# CircuitPlayground_ESP12_555_004.net
KiCad netlist of a schematic drawn in EAGLE
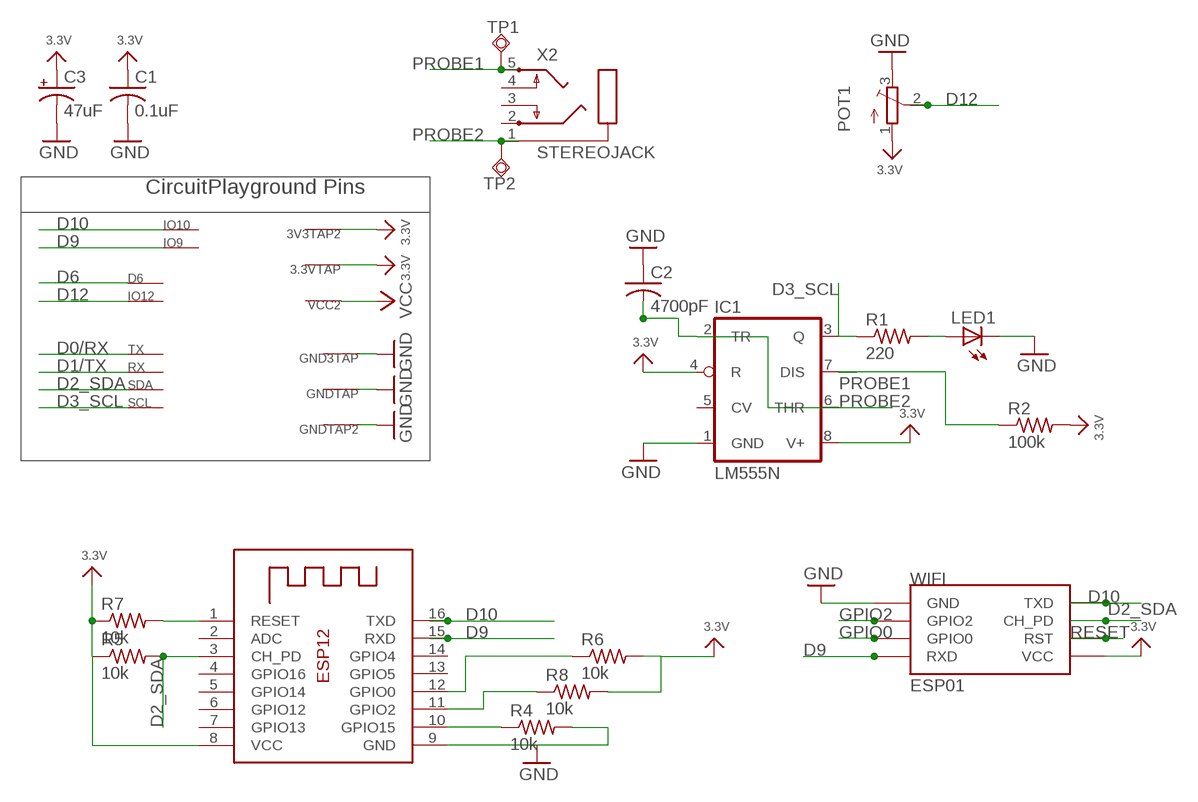
[diagram p0: schematic, sheet 1]

(export (version "E")
  (design (tool "Eeschema 10.0.6"))
  (components
    (comp (ref "3.3VTAP")
      (value "SEWTAP-ALLIGATOR")
      (footprint "eagle-import:SEWALLI")
      (libsource (lib "eagle-import") (part "SEWTAP-ALLIGATOR"))
    )
    (comp (ref "3V3TAP2")
      (value "SEWTAP-ALLIGATOR")
      (footprint "eagle-import:SEWALLI")
      (libsource (lib "eagle-import") (part "SEWTAP-ALLIGATOR"))
    )
    (comp (ref "C1")
      (value "0.1uF")
      (footprint "eagle-import:C025-030X050")
      (libsource (lib "eagle-import") (part "C-US025-030X050"))
    )
    (comp (ref "C2")
      (value "4700pF")
      (footprint "eagle-import:C025-030X050")
      (libsource (lib "eagle-import") (part "C-US025-030X050"))
    )
    (comp (ref "C3")
      (value "47uF")
      (footprint "eagle-import:E2-4")
      (libsource (lib "eagle-import") (part "CPOL-USE2-4"))
    )
    (comp (ref "D6")
      (value "SEWTAP-ALLIGATOR")
      (footprint "eagle-import:SEWALLI")
      (libsource (lib "eagle-import") (part "SEWTAP-ALLIGATOR"))
    )
    (comp (ref "GND3TAP")
      (value "SEWTAP-ALLIGATOR")
      (footprint "eagle-import:SEWALLI")
      (libsource (lib "eagle-import") (part "SEWTAP-ALLIGATOR"))
    )
    (comp (ref "GNDTAP")
      (value "SEWTAP-ALLIGATOR")
      (footprint "eagle-import:SEWALLI")
      (libsource (lib "eagle-import") (part "SEWTAP-ALLIGATOR"))
    )
    (comp (ref "GNDTAP2")
      (value "SEWTAP-ALLIGATOR")
      (footprint "eagle-import:SEWALLI")
      (libsource (lib "eagle-import") (part "SEWTAP-ALLIGATOR"))
    )
    (comp (ref "IC1")
      (value "LM555N")
      (footprint "eagle-import:DIL08-ROUND")
      (libsource (lib "eagle-import") (part "555NLM"))
    )
    (comp (ref "IO9")
      (value "SEWTAP-ALLIGATOR")
      (footprint "eagle-import:SEWALLI")
      (libsource (lib "eagle-import") (part "SEWTAP-ALLIGATOR"))
    )
    (comp (ref "IO10")
      (value "SEWTAP-ALLIGATOR")
      (footprint "eagle-import:SEWALLI")
      (libsource (lib "eagle-import") (part "SEWTAP-ALLIGATOR"))
    )
    (comp (ref "IO12")
      (value "SEWTAP-ALLIGATOR")
      (footprint "eagle-import:SEWALLI")
      (libsource (lib "eagle-import") (part "SEWTAP-ALLIGATOR"))
    )
    (comp (ref "LED1")
      (value "LED5MM")
      (footprint "eagle-import:LED5MM")
      (libsource (lib "eagle-import") (part "LED5MM"))
    )
    (comp (ref "POT1")
      (value "TRIMPOT3386")
      (footprint "eagle-import:TRIM-3386")
      (libsource (lib "eagle-import") (part "TRIMPOT3386"))
    )
    (comp (ref "R1")
      (value "220")
      (footprint "eagle-import:R1206")
      (libsource (lib "eagle-import") (part "R-US_R1206"))
    )
    (comp (ref "R2")
      (value "100k")
      (footprint "eagle-import:R1206")
      (libsource (lib "eagle-import") (part "R-US_R1206"))
    )
    (comp (ref "R4")
      (value "10k")
      (footprint "eagle-import:R1206")
      (libsource (lib "eagle-import") (part "R-US_R1206"))
    )
    (comp (ref "R5")
      (value "10k")
      (footprint "eagle-import:R1206")
      (libsource (lib "eagle-import") (part "R-US_R1206"))
    )
    (comp (ref "R6")
      (value "10k")
      (footprint "eagle-import:R1206")
      (libsource (lib "eagle-import") (part "R-US_R1206"))
    )
    (comp (ref "R7")
      (value "10k")
      (footprint "eagle-import:R1206")
      (libsource (lib "eagle-import") (part "R-US_R1206"))
    )
    (comp (ref "R8")
      (value "10k")
      (footprint "eagle-import:R1206")
      (libsource (lib "eagle-import") (part "R-US_R1206"))
    )
    (comp (ref "RX")
      (value "SEWTAP-ALLIGATOR")
      (footprint "eagle-import:SEWALLI")
      (libsource (lib "eagle-import") (part "SEWTAP-ALLIGATOR"))
    )
    (comp (ref "SCL")
      (value "SEWTAP-ALLIGATOR")
      (footprint "eagle-import:SEWALLI")
      (libsource (lib "eagle-import") (part "SEWTAP-ALLIGATOR"))
    )
    (comp (ref "SDA")
      (value "SEWTAP-ALLIGATOR")
      (footprint "eagle-import:SEWALLI")
      (libsource (lib "eagle-import") (part "SEWTAP-ALLIGATOR"))
    )
    (comp (ref "TP1")
      (value "TPSQTP20R")
      (footprint "eagle-import:TP20R")
      (libsource (lib "eagle-import") (part "TPSQTP20R"))
    )
    (comp (ref "TP2")
      (value "TPSQTP20R")
      (footprint "eagle-import:TP20R")
      (libsource (lib "eagle-import") (part "TPSQTP20R"))
    )
    (comp (ref "TX")
      (value "SEWTAP-ALLIGATOR")
      (footprint "eagle-import:SEWALLI")
      (libsource (lib "eagle-import") (part "SEWTAP-ALLIGATOR"))
    )
    (comp (ref "VCC2")
      (value "SEWTAP-ALLIGATOR")
      (footprint "eagle-import:SEWALLI")
      (libsource (lib "eagle-import") (part "SEWTAP-ALLIGATOR"))
    )
    (comp (ref "WIFI")
      (value "ESP01")
      (footprint "eagle-import:ESP01")
      (libsource (lib "eagle-import") (part "ESP01"))
    )
    (comp (ref "X1")
      (value "ESP-12")
      (footprint "eagle-import:ESP-12")
      (libsource (lib "eagle-import") (part "ESP-12"))
    )
    (comp (ref "X2")
      (value "STEREOJACK")
      (footprint "eagle-import:STX3100")
      (libsource (lib "eagle-import") (part "STEREOJACK"))
    )
  )
  (nets
    (net (code "1") (name "/D0{slash}RX") (class "Default")
      (node (ref "TX") (pin "P$1") (pinfunction "SEW_P$1") (pintype "bidirectional"))
    )
    (net (code "2") (name "/D1{slash}TX") (class "Default")
      (node (ref "RX") (pin "P$1") (pinfunction "SEW_P$1") (pintype "bidirectional"))
    )
    (net (code "3") (name "/D2_SDA") (class "Default")
      (node (ref "R5") (pin "2") (pinfunction "2_2") (pintype "passive"))
      (node (ref "SDA") (pin "P$1") (pinfunction "SEW_P$1") (pintype "bidirectional"))
      (node (ref "WIFI") (pin "CH_PD") (pinfunction "CH_PD_CH_PD") (pintype "bidirectional"))
      (node (ref "X1") (pin "3") (pinfunction "CH_PD_3") (pintype "input"))
    )
    (net (code "4") (name "/D3_SCL") (class "Default")
      (node (ref "IC1") (pin "3") (pinfunction "Q_3") (pintype "output"))
      (node (ref "R1") (pin "1") (pinfunction "1_1") (pintype "passive"))
      (node (ref "SCL") (pin "P$1") (pinfunction "SEW_P$1") (pintype "bidirectional"))
    )
    (net (code "5") (name "/D6") (class "Default")
      (node (ref "D6") (pin "P$1") (pinfunction "SEW_P$1") (pintype "bidirectional"))
    )
    (net (code "6") (name "/D9") (class "Default")
      (node (ref "IO9") (pin "P$1") (pinfunction "SEW_P$1") (pintype "bidirectional"))
      (node (ref "WIFI") (pin "RX") (pinfunction "RXD_RX") (pintype "bidirectional"))
      (node (ref "X1") (pin "15") (pinfunction "RXD_15") (pintype "input"))
    )
    (net (code "7") (name "/D10") (class "Default")
      (node (ref "IO10") (pin "P$1") (pinfunction "SEW_P$1") (pintype "bidirectional"))
      (node (ref "WIFI") (pin "TX") (pinfunction "TXD_TX") (pintype "bidirectional"))
      (node (ref "X1") (pin "16") (pinfunction "TXD_16") (pintype "output"))
    )
    (net (code "8") (name "/D12") (class "Default")
      (node (ref "IO12") (pin "P$1") (pinfunction "SEW_P$1") (pintype "bidirectional"))
      (node (ref "POT1") (pin "2") (pinfunction "S_2") (pintype "passive"))
    )
    (net (code "9") (name "/GPIO0") (class "Default")
      (node (ref "R6") (pin "1") (pinfunction "1_1") (pintype "passive"))
      (node (ref "WIFI") (pin "GPIO0") (pinfunction "GPIO0_GPIO0") (pintype "bidirectional"))
      (node (ref "X1") (pin "12") (pinfunction "GPIO0_12") (pintype "bidirectional"))
    )
    (net (code "10") (name "/GPIO2") (class "Default")
      (node (ref "R8") (pin "1") (pinfunction "1_1") (pintype "passive"))
      (node (ref "WIFI") (pin "GPIO2") (pinfunction "GPIO2_GPIO2") (pintype "bidirectional"))
      (node (ref "X1") (pin "11") (pinfunction "GPIO2_11") (pintype "bidirectional"))
    )
    (net (code "11") (name "/PROBE1") (class "Default")
      (node (ref "IC1") (pin "7") (pinfunction "DIS_7") (pintype "input"))
      (node (ref "R2") (pin "1") (pinfunction "1_1") (pintype "passive"))
      (node (ref "TP1") (pin "TP") (pinfunction "TP_TP") (pintype "input"))
      (node (ref "X2") (pin "5") (pinfunction "5_5") (pintype "passive"))
    )
    (net (code "12") (name "/PROBE2") (class "Default")
      (node (ref "C2") (pin "2") (pinfunction "2_2") (pintype "passive"))
      (node (ref "IC1") (pin "2") (pinfunction "TR_2") (pintype "input"))
      (node (ref "IC1") (pin "6") (pinfunction "THR_6") (pintype "input"))
      (node (ref "TP2") (pin "TP") (pinfunction "TP_TP") (pintype "input"))
      (node (ref "X2") (pin "1") (pinfunction "1_1") (pintype "passive"))
    )
    (net (code "13") (name "/RESET") (class "Default")
      (node (ref "R7") (pin "2") (pinfunction "2_2") (pintype "passive"))
      (node (ref "WIFI") (pin "RST") (pinfunction "RST_RST") (pintype "bidirectional"))
      (node (ref "X1") (pin "1") (pinfunction "RESET_1") (pintype "input"))
    )
    (net (code "14") (name "3.3V") (class "Default")
      (node (ref "3.3VTAP") (pin "P$1") (pinfunction "SEW_P$1") (pintype "bidirectional"))
      (node (ref "3V3TAP2") (pin "P$1") (pinfunction "SEW_P$1") (pintype "bidirectional"))
      (node (ref "C1") (pin "1") (pinfunction "1_1") (pintype "passive"))
      (node (ref "C3") (pin "+") (pinfunction "+_+") (pintype "passive"))
      (node (ref "IC1") (pin "4") (pinfunction "R_4") (pintype "input"))
      (node (ref "IC1") (pin "8") (pinfunction "V+_8") (pintype "power_in"))
      (node (ref "POT1") (pin "1") (pinfunction "A_1") (pintype "passive"))
      (node (ref "R2") (pin "2") (pinfunction "2_2") (pintype "passive"))
      (node (ref "R5") (pin "1") (pinfunction "1_1") (pintype "passive"))
      (node (ref "R6") (pin "2") (pinfunction "2_2") (pintype "passive"))
      (node (ref "R7") (pin "1") (pinfunction "1_1") (pintype "passive"))
      (node (ref "R8") (pin "2") (pinfunction "2_2") (pintype "passive"))
      (node (ref "WIFI") (pin "VCC") (pinfunction "VCC_VCC") (pintype "bidirectional"))
      (node (ref "X1") (pin "8") (pinfunction "VCC_8") (pintype "power_in"))
    )
    (net (code "15") (name "GND") (class "Default")
      (node (ref "C1") (pin "2") (pinfunction "2_2") (pintype "passive"))
      (node (ref "C2") (pin "1") (pinfunction "1_1") (pintype "passive"))
      (node (ref "C3") (pin "-") (pinfunction "-_-") (pintype "passive"))
      (node (ref "GND3TAP") (pin "P$1") (pinfunction "SEW_P$1") (pintype "bidirectional"))
      (node (ref "GNDTAP") (pin "P$1") (pinfunction "SEW_P$1") (pintype "bidirectional"))
      (node (ref "GNDTAP2") (pin "P$1") (pinfunction "SEW_P$1") (pintype "bidirectional"))
      (node (ref "IC1") (pin "1") (pinfunction "GND_1") (pintype "power_in"))
      (node (ref "LED1") (pin "K") (pinfunction "C_K") (pintype "passive"))
      (node (ref "POT1") (pin "3") (pinfunction "E_3") (pintype "passive"))
      (node (ref "R4") (pin "2") (pinfunction "2_2") (pintype "passive"))
      (node (ref "WIFI") (pin "GND") (pinfunction "GND_GND") (pintype "bidirectional"))
      (node (ref "X1") (pin "9") (pinfunction "GND_9") (pintype "power_in"))
    )
    (net (code "16") (name "Net-(LED1-PadA)") (class "Default")
      (node (ref "LED1") (pin "A") (pinfunction "A_A") (pintype "passive"))
      (node (ref "R1") (pin "2") (pinfunction "2_2") (pintype "passive"))
    )
    (net (code "17") (name "Net-(X1-GPIO15)") (class "Default")
      (node (ref "R4") (pin "1") (pinfunction "1_1") (pintype "passive"))
      (node (ref "X1") (pin "10") (pinfunction "GPIO15_10") (pintype "bidirectional"))
    )
    (net (code "18") (name "VCC") (class "Default")
      (node (ref "VCC2") (pin "P$1") (pinfunction "SEW_P$1") (pintype "bidirectional"))
    )
    (net (code "19") (name "unconnected-(IC1-CV-Pad5)") (class "Default")
      (node (ref "IC1") (pin "5") (pinfunction "CV_5") (pintype "input"))
    )
    (net (code "20") (name "unconnected-(X1-ADC-Pad2)") (class "Default")
      (node (ref "X1") (pin "2") (pinfunction "ADC_2") (pintype "passive"))
    )
    (net (code "21") (name "unconnected-(X1-GPIO4-Pad14)") (class "Default")
      (node (ref "X1") (pin "14") (pinfunction "GPIO4_14") (pintype "bidirectional"))
    )
    (net (code "22") (name "unconnected-(X1-GPIO5-Pad13)") (class "Default")
      (node (ref "X1") (pin "13") (pinfunction "GPIO5_13") (pintype "bidirectional"))
    )
    (net (code "23") (name "unconnected-(X1-GPIO12-Pad6)") (class "Default")
      (node (ref "X1") (pin "6") (pinfunction "GPIO12_6") (pintype "bidirectional"))
    )
    (net (code "24") (name "unconnected-(X1-GPIO13-Pad7)") (class "Default")
      (node (ref "X1") (pin "7") (pinfunction "GPIO13_7") (pintype "bidirectional"))
    )
    (net (code "25") (name "unconnected-(X1-GPIO14-Pad5)") (class "Default")
      (node (ref "X1") (pin "5") (pinfunction "GPIO14_5") (pintype "bidirectional"))
    )
    (net (code "26") (name "unconnected-(X1-GPIO16-Pad4)") (class "Default")
      (node (ref "X1") (pin "4") (pinfunction "GPIO16_4") (pintype "bidirectional"))
    )
    (net (code "27") (name "unconnected-(X2-Pad2)") (class "Default")
      (node (ref "X2") (pin "2") (pinfunction "2_2") (pintype "passive"))
    )
    (net (code "28") (name "unconnected-(X2-Pad3)") (class "Default")
      (node (ref "X2") (pin "3") (pinfunction "3_3") (pintype "passive"))
    )
    (net (code "29") (name "unconnected-(X2-Pad4)") (class "Default")
      (node (ref "X2") (pin "4") (pinfunction "4_4") (pintype "passive"))
    )
  )
)
